# PCB_schematic_for_light_switch.net
KiCad netlist of a schematic drawn in Altium Designer
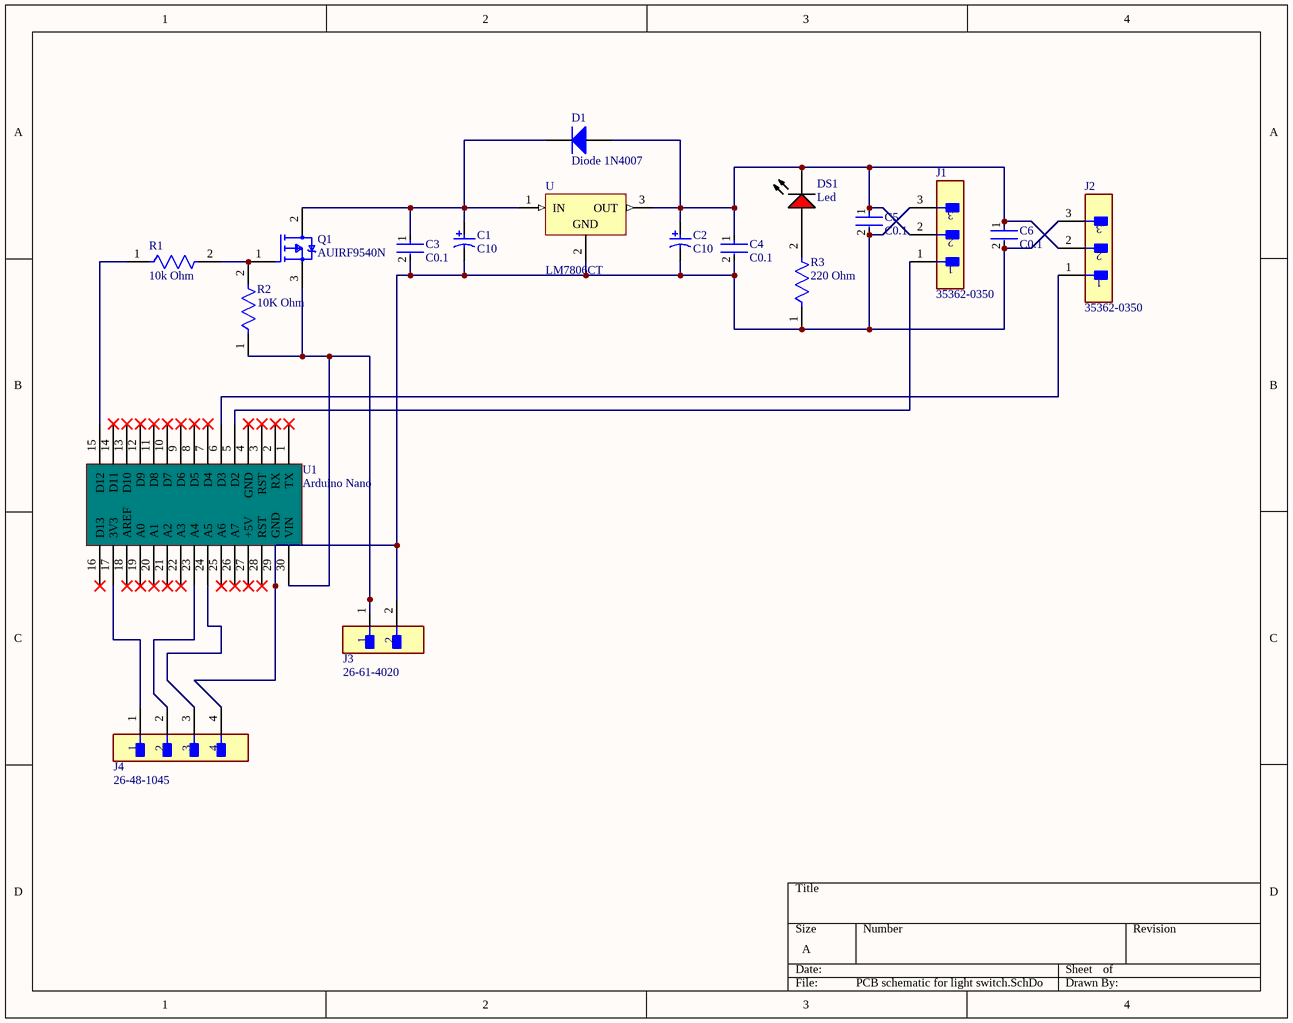
[diagram p0: PCB schematic for light switch.SchDoc]

(export (version "E")
  (design (tool "Eeschema 10.0.6"))
  (components
    (comp (ref "C1")
      (value "C10")
      (footprint "CAPPR55-200-1100X500X1200")
      (description "Aluminum Electrolytic Capacitor, 10 uF, +/- 20%, 50 V, -40 to 85 degC, 2-Pin THD, RoHS, Bulk")
      (fields (field (name "MANUFACTURER") "Panasonic") (field (name "TOLERANCE") "20%"))
      (libsource (lib "Altium Content Vault") (part "CAP-P-2"))
    )
    (comp (ref "C2")
      (value "C10")
      (footprint "CAPPR55-200-1100X500X1200")
      (description "Aluminum Electrolytic Capacitor, 10 uF, +/- 20%, 50 V, -40 to 85 degC, 2-Pin THD, RoHS, Bulk")
      (fields (field (name "MANUFACTURER") "Panasonic") (field (name "TOLERANCE") "20%"))
      (libsource (lib "Altium Content Vault") (part "CAP-P-2"))
    )
    (comp (ref "C3")
      (value "C0.1")
      (footprint "FP-K15H5-MFG")
      (description "CAP CER 0.1UF 50V X7R RADIAL")
      (fields (field (name "TOLERANCE") "10%") (field (name "VOLTAGE") "50V"))
      (libsource (lib "Altium Content Vault") (part "02cd4be3c70576c341d710602a673aa"))
    )
    (comp (ref "C4")
      (value "C0.1")
      (footprint "FP-K15H5-MFG")
      (description "CAP CER 0.1UF 50V X7R RADIAL")
      (fields (field (name "TOLERANCE") "10%") (field (name "VOLTAGE") "50V"))
      (libsource (lib "Altium Content Vault") (part "02cd4be3c70576c341d710602a673aa"))
    )
    (comp (ref "C5")
      (value "C0.1")
      (footprint "FP-K15H5-MFG")
      (description "CAP CER 0.1UF 50V X7R RADIAL")
      (fields (field (name "TOLERANCE") "10%") (field (name "VOLTAGE") "50V"))
      (libsource (lib "Altium Content Vault") (part "02cd4be3c70576c341d710602a673aa"))
    )
    (comp (ref "C6")
      (value "C0.1")
      (footprint "FP-K15H5-MFG")
      (description "CAP CER 0.1UF 50V X7R RADIAL")
      (fields (field (name "TOLERANCE") "10%") (field (name "VOLTAGE") "50V"))
      (libsource (lib "Altium Content Vault") (part "02cd4be3c70576c341d710602a673aa"))
    )
    (comp (ref "D1")
      (value "Diode 1N4007")
      (footprint "DO-41")
      (description "1 Amp General Purpose Rectifier")
      (fields (field (name "PUBLISHER") "Altium Limited"))
      (libsource (lib "Miscellaneous Devices") (part "Diode 1N4007"))
    )
    (comp (ref "DS1")
      (value "Led")
      (footprint "AVAG-HLMP-3301-2")
      (description "T-1 3/4 (5 mm) Diffused LED Lamp, 1.9 V, -40 to 100 degC, 2-Pin THD, RoHS, Bulk")
      (fields (field (name "MANUFACTURER") "Avago"))
      (libsource (lib "Altium Content Vault") (part "LED-RED-K1A2-2"))
    )
    (comp (ref "J1")
      (value "35362-0350")
      (footprint "FP-35362-0350-MFG")
      (description "CONN HEADER VERT 3POS 2MM")
      (libsource (lib "Altium Content Vault") (part "0d3f023dd272f625e17a2be33dea85f"))
    )
    (comp (ref "J2")
      (value "35362-0350")
      (footprint "FP-35362-0350-MFG")
      (description "CONN HEADER VERT 3POS 2MM")
      (libsource (lib "Altium Content Vault") (part "0d3f023dd272f625e17a2be33dea85f"))
    )
    (comp (ref "J3")
      (value "26-61-4020")
      (footprint "FP-26-61-4020-MFG")
      (libsource (lib "Altium Content Vault") (part "3bc925449376181038e59eaffc5286c"))
    )
    (comp (ref "J4")
      (value "26-48-1045")
      (footprint "FP-26-48-1045-MFG")
      (libsource (lib "Altium Content Vault") (part "299a8cea1bdcbc3624fe62c390fa72c"))
    )
    (comp (ref "Q1")
      (value "AUIRF9540N")
      (footprint "FP-TO-220AB-MFG")
      (description "AUIRF9540N Automotive Q101 -100V Single P-Channel HEXFET Power MOSFET in a TO-220AB Package")
      (libsource (lib "Altium Content Vault") (part "0a5270dd5e0f7d999c9a43bdc78dc18"))
    )
    (comp (ref "R1")
      (value "10k Ohm")
      (footprint "FP-CF18-MFG")
      (description "RES 10K OHM 1/8W 5% CF AXIAL")
      (fields
        (field (name "MANUFACTURER PART NUMBER") "CF18JT10K0")
        (field (name "MANUFACTURER") "Stackpole Electronics")
      )
      (libsource (lib "Altium Content Vault") (part "1029c3af85768c4190bb7ad29bc67b5"))
    )
    (comp (ref "R2")
      (value "10K Ohm")
      (footprint "FP-CF18-MFG")
      (description "RES 10K OHM 1/8W 5% CF AXIAL")
      (fields
        (field (name "MANUFACTURER PART NUMBER") "CF18JT10K0")
        (field (name "MANUFACTURER") "Stackpole Electronics")
      )
      (libsource (lib "Altium Content Vault") (part "1029c3af85768c4190bb7ad29bc67b5"))
    )
    (comp (ref "R3")
      (value "220 Ohm")
      (footprint "FP-CF18-MFG")
      (description "RES 10K OHM 1/8W 5% CF AXIAL")
      (fields
        (field (name "MANUFACTURER PART NUMBER") "CF18JT10K0")
        (field (name "MANUFACTURER") "Stackpole Electronics")
      )
      (libsource (lib "Altium Content Vault") (part "1029c3af85768c4190bb7ad29bc67b5"))
    )
    (comp (ref "U")
      (value "LM7806CT")
      (footprint "FAIR-TO-220-3")
      (description "Positive Voltage Regulator, 5 V, 1 A, -40 to 125 degC, 3-Pin TO-220, RoHS, Tube")
      (fields (field (name "MANUFACTURER") "FairchildSemiconductor"))
      (libsource (lib "Altium Content Vault") (part "FAIR-LM7805CT-TO220-3"))
    )
    (comp (ref "U1")
      (value "Arduino Nano")
      (footprint "PCBComponent_1")
      (libsource (lib "Nano") (part "Component_1"))
    )
  )
  (nets
    (net (code "1") (name "Net-(D1-A)") (class "Default")
      (node (ref "C2") (pin "1") (pinfunction "1_1") (pintype "passive"))
      (node (ref "C4") (pin "1") (pinfunction "1_1") (pintype "passive"))
      (node (ref "C5") (pin "1") (pinfunction "1_1") (pintype "passive"))
      (node (ref "C6") (pin "1") (pinfunction "1_1") (pintype "passive"))
      (node (ref "D1") (pin "1") (pinfunction "A_1") (pintype "passive"))
      (node (ref "DS1") (pin "1") (pinfunction "K_1") (pintype "passive"))
      (node (ref "J1") (pin "2") (pinfunction "2_2") (pintype "passive"))
      (node (ref "J2") (pin "2") (pinfunction "2_2") (pintype "passive"))
      (node (ref "U") (pin "3") (pinfunction "OUT_3") (pintype "output"))
    )
    (net (code "2") (name "Net-(D1-K)") (class "Default")
      (node (ref "C1") (pin "1") (pinfunction "1_1") (pintype "passive"))
      (node (ref "C3") (pin "1") (pinfunction "1_1") (pintype "passive"))
      (node (ref "D1") (pin "2") (pinfunction "K_2") (pintype "passive"))
      (node (ref "Q1") (pin "2") (pinfunction "D_2") (pintype "passive"))
      (node (ref "U") (pin "1") (pinfunction "IN_1") (pintype "input"))
    )
    (net (code "3") (name "Net-(DS1-A)") (class "Default")
      (node (ref "DS1") (pin "2") (pinfunction "A_2") (pintype "passive"))
      (node (ref "R3") (pin "2") (pinfunction "2_2") (pintype "passive"))
    )
    (net (code "4") (name "Net-(Q1-G)") (class "Default")
      (node (ref "Q1") (pin "1") (pinfunction "G_1") (pintype "passive"))
      (node (ref "R1") (pin "2") (pinfunction "2_2") (pintype "passive"))
      (node (ref "R2") (pin "2") (pinfunction "2_2") (pintype "passive"))
    )
    (net (code "5") (name "Net-(Q1-S)") (class "Default")
      (node (ref "J3") (pin "1") (pinfunction "1_1") (pintype "passive"))
      (node (ref "Q1") (pin "3") (pinfunction "S_3") (pintype "passive"))
      (node (ref "R2") (pin "1") (pinfunction "1_1") (pintype "passive"))
      (node (ref "U1") (pin "30") (pinfunction "VIN_30") (pintype "passive"))
    )
    (net (code "6") (name "Net-(U-GND)") (class "Default")
      (node (ref "C1") (pin "2") (pinfunction "2_2") (pintype "passive"))
      (node (ref "C2") (pin "2") (pinfunction "2_2") (pintype "passive"))
      (node (ref "C3") (pin "2") (pinfunction "2_2") (pintype "passive"))
      (node (ref "C4") (pin "2") (pinfunction "2_2") (pintype "passive"))
      (node (ref "C5") (pin "2") (pinfunction "2_2") (pintype "passive"))
      (node (ref "C6") (pin "2") (pinfunction "2_2") (pintype "passive"))
      (node (ref "J1") (pin "3") (pinfunction "3_3") (pintype "passive"))
      (node (ref "J2") (pin "3") (pinfunction "3_3") (pintype "passive"))
      (node (ref "J3") (pin "2") (pinfunction "2_2") (pintype "passive"))
      (node (ref "J4") (pin "4") (pinfunction "4_4") (pintype "passive"))
      (node (ref "R3") (pin "1") (pinfunction "1_1") (pintype "passive"))
      (node (ref "U") (pin "2") (pinfunction "GND_2") (pintype "power_in"))
      (node (ref "U1") (pin "29") (pinfunction "GND_29") (pintype "passive"))
    )
    (net (code "7") (name "Net-(U1-3V3)") (class "Default")
      (node (ref "J4") (pin "1") (pinfunction "1_1") (pintype "passive"))
      (node (ref "U1") (pin "17") (pinfunction "3V3_17") (pintype "passive"))
    )
    (net (code "8") (name "Net-(U1-A4)") (class "Default")
      (node (ref "J4") (pin "2") (pinfunction "2_2") (pintype "passive"))
      (node (ref "U1") (pin "23") (pinfunction "A4_23") (pintype "passive"))
    )
    (net (code "9") (name "Net-(U1-A5)") (class "Default")
      (node (ref "J4") (pin "3") (pinfunction "3_3") (pintype "passive"))
      (node (ref "U1") (pin "24") (pinfunction "A5_24") (pintype "passive"))
    )
    (net (code "10") (name "Net-(U1-D2)") (class "Default")
      (node (ref "J1") (pin "1") (pinfunction "1_1") (pintype "passive"))
      (node (ref "U1") (pin "5") (pinfunction "D2_5") (pintype "passive"))
    )
    (net (code "11") (name "Net-(U1-D3)") (class "Default")
      (node (ref "J2") (pin "1") (pinfunction "1_1") (pintype "passive"))
      (node (ref "U1") (pin "6") (pinfunction "D3_6") (pintype "passive"))
    )
    (net (code "12") (name "Net-(U1-D12)") (class "Default")
      (node (ref "R1") (pin "1") (pinfunction "1_1") (pintype "passive"))
      (node (ref "U1") (pin "15") (pinfunction "D12_15") (pintype "passive"))
    )
    (net (code "13") (name "unconnected-(U1-+5V-Pad27)") (class "Default")
      (node (ref "U1") (pin "27") (pinfunction "+5V_27") (pintype "passive+no_connect"))
    )
    (net (code "14") (name "unconnected-(U1-A0-Pad19)") (class "Default")
      (node (ref "U1") (pin "19") (pinfunction "A0_19") (pintype "passive+no_connect"))
    )
    (net (code "15") (name "unconnected-(U1-A1-Pad20)") (class "Default")
      (node (ref "U1") (pin "20") (pinfunction "A1_20") (pintype "passive+no_connect"))
    )
    (net (code "16") (name "unconnected-(U1-A2-Pad21)") (class "Default")
      (node (ref "U1") (pin "21") (pinfunction "A2_21") (pintype "passive+no_connect"))
    )
    (net (code "17") (name "unconnected-(U1-A3-Pad22)") (class "Default")
      (node (ref "U1") (pin "22") (pinfunction "A3_22") (pintype "passive+no_connect"))
    )
    (net (code "18") (name "unconnected-(U1-A6-Pad25)") (class "Default")
      (node (ref "U1") (pin "25") (pinfunction "A6_25") (pintype "passive+no_connect"))
    )
    (net (code "19") (name "unconnected-(U1-A7-Pad26)") (class "Default")
      (node (ref "U1") (pin "26") (pinfunction "A7_26") (pintype "passive+no_connect"))
    )
    (net (code "20") (name "unconnected-(U1-AREF-Pad18)") (class "Default")
      (node (ref "U1") (pin "18") (pinfunction "AREF_18") (pintype "passive+no_connect"))
    )
    (net (code "21") (name "unconnected-(U1-D4-Pad7)") (class "Default")
      (node (ref "U1") (pin "7") (pinfunction "D4_7") (pintype "passive+no_connect"))
    )
    (net (code "22") (name "unconnected-(U1-D5-Pad8)") (class "Default")
      (node (ref "U1") (pin "8") (pinfunction "D5_8") (pintype "passive+no_connect"))
    )
    (net (code "23") (name "unconnected-(U1-D6-Pad9)") (class "Default")
      (node (ref "U1") (pin "9") (pinfunction "D6_9") (pintype "passive+no_connect"))
    )
    (net (code "24") (name "unconnected-(U1-D7-Pad10)") (class "Default")
      (node (ref "U1") (pin "10") (pinfunction "D7_10") (pintype "passive+no_connect"))
    )
    (net (code "25") (name "unconnected-(U1-D8-Pad11)") (class "Default")
      (node (ref "U1") (pin "11") (pinfunction "D8_11") (pintype "passive+no_connect"))
    )
    (net (code "26") (name "unconnected-(U1-D9-Pad12)") (class "Default")
      (node (ref "U1") (pin "12") (pinfunction "D9_12") (pintype "passive+no_connect"))
    )
    (net (code "27") (name "unconnected-(U1-D10-Pad13)") (class "Default")
      (node (ref "U1") (pin "13") (pinfunction "D10_13") (pintype "passive+no_connect"))
    )
    (net (code "28") (name "unconnected-(U1-D11-Pad14)") (class "Default")
      (node (ref "U1") (pin "14") (pinfunction "D11_14") (pintype "passive+no_connect"))
    )
    (net (code "29") (name "unconnected-(U1-D13-Pad16)") (class "Default")
      (node (ref "U1") (pin "16") (pinfunction "D13_16") (pintype "passive+no_connect"))
    )
    (net (code "30") (name "unconnected-(U1-GND-Pad4)") (class "Default")
      (node (ref "U1") (pin "4") (pinfunction "GND_4") (pintype "passive+no_connect"))
    )
    (net (code "31") (name "unconnected-(U1-RST-Pad3)") (class "Default")
      (node (ref "U1") (pin "3") (pinfunction "RST_3") (pintype "passive+no_connect"))
    )
    (net (code "32") (name "unconnected-(U1-RST-Pad28)") (class "Default")
      (node (ref "U1") (pin "28") (pinfunction "RST_28") (pintype "passive+no_connect"))
    )
    (net (code "33") (name "unconnected-(U1-RX-Pad2)") (class "Default")
      (node (ref "U1") (pin "2") (pinfunction "RX_2") (pintype "passive+no_connect"))
    )
    (net (code "34") (name "unconnected-(U1-TX-Pad1)") (class "Default")
      (node (ref "U1") (pin "1") (pinfunction "TX_1") (pintype "passive+no_connect"))
    )
  )
)
